# V1_1.net
KiCad netlist of a schematic drawn in Altium Designer
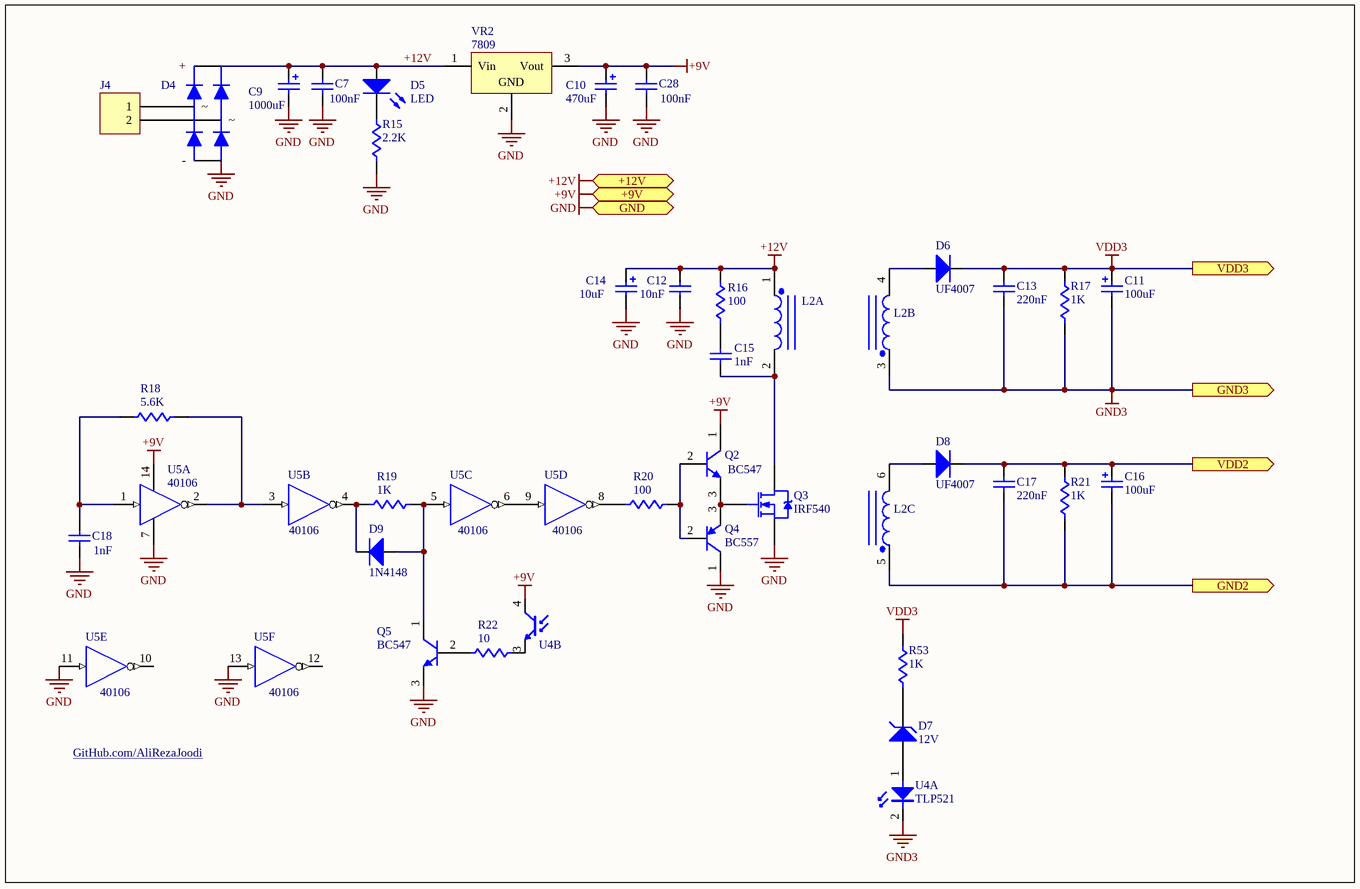
[diagram p0: V1.1.SchDoc]

(export (version "E")
  (design (tool "Eeschema 10.0.6"))
  (components
    (comp (ref "C7")
      (value "100nF")
      (footprint "CAPNTO2.54-3.05x1.78A")
      (description "Capacitor")
      (fields
        (field (name "MANUFACTURER") "Generic Components")
        (field (name "Comment") "Cap")
        (field (name "PUBLISHER") "Altium Limited")
      )
      (libsource (lib "Miscellaneous Devices") (part "Cap"))
    )
    (comp (ref "C9")
      (value "1000uF")
      (footprint "CAPPR5-10x12.5")
      (description "Polarized Capacitor (Radial)")
      (fields
        (field (name "MANUFACTURER") "Generic Components")
        (field (name "Comment") "Cap Pol1")
        (field (name "PUBLISHER") "Altium Limited")
      )
      (libsource (lib "Miscellaneous Devices") (part "Cap Pol1"))
    )
    (comp (ref "C10")
      (value "470uF")
      (footprint "CAPPR5-10x12.5")
      (description "Polarized Capacitor (Radial)")
      (fields
        (field (name "MANUFACTURER") "Generic Components")
        (field (name "Comment") "Cap Pol1")
        (field (name "PUBLISHER") "Altium Limited")
      )
      (libsource (lib "Miscellaneous Devices") (part "Cap Pol1"))
    )
    (comp (ref "C11")
      (value "100uF")
      (footprint "CAPPR2.5-6.3x5")
      (description "Polarized Capacitor (Radial)")
      (fields
        (field (name "MANUFACTURER") "Generic Components")
        (field (name "Comment") "Cap Pol1")
        (field (name "PUBLISHER") "Altium Limited")
      )
      (libsource (lib "Miscellaneous Devices") (part "Cap Pol1"))
    )
    (comp (ref "C12")
      (value "10nF")
      (footprint "CAPNTO2.54-3.05x1.78A")
      (description "Capacitor")
      (fields
        (field (name "MANUFACTURER") "Generic Components")
        (field (name "Comment") "Cap")
        (field (name "PUBLISHER") "Altium Limited")
      )
      (libsource (lib "Miscellaneous Devices") (part "Cap"))
    )
    (comp (ref "C13")
      (value "220nF")
      (footprint "CAPNTO5.08-7.37x3.94")
      (description "Capacitor")
      (fields
        (field (name "MANUFACTURER") "Generic Components")
        (field (name "Comment") "Cap")
        (field (name "PUBLISHER") "Altium Limited")
      )
      (libsource (lib "Miscellaneous Devices") (part "Cap"))
    )
    (comp (ref "C14")
      (value "10uF")
      (footprint "CAPPR2.5-6.3x5")
      (description "Polarized Capacitor (Radial)")
      (fields
        (field (name "MANUFACTURER") "Generic Components")
        (field (name "Comment") "Cap Pol1")
        (field (name "PUBLISHER") "Altium Limited")
      )
      (libsource (lib "Miscellaneous Devices") (part "Cap Pol1"))
    )
    (comp (ref "C15")
      (value "1nF")
      (footprint "CAPNTO2.54-3.56x2.03")
      (description "Capacitor")
      (fields
        (field (name "MANUFACTURER") "Generic Components")
        (field (name "Comment") "Cap")
        (field (name "PUBLISHER") "Altium Limited")
      )
      (libsource (lib "Miscellaneous Devices") (part "Cap"))
    )
    (comp (ref "C16")
      (value "100uF")
      (footprint "CAPPR2.5-6.3x5")
      (description "Polarized Capacitor (Radial)")
      (fields
        (field (name "MANUFACTURER") "Generic Components")
        (field (name "Comment") "Cap Pol1")
        (field (name "PUBLISHER") "Altium Limited")
      )
      (libsource (lib "Miscellaneous Devices") (part "Cap Pol1"))
    )
    (comp (ref "C17")
      (value "220nF")
      (footprint "CAPNTO5.08-7.37x3.94")
      (description "Capacitor")
      (fields
        (field (name "MANUFACTURER") "Generic Components")
        (field (name "Comment") "Cap")
        (field (name "PUBLISHER") "Altium Limited")
      )
      (libsource (lib "Miscellaneous Devices") (part "Cap"))
    )
    (comp (ref "C18")
      (value "1nF")
      (footprint "CAPNTO2.54-3.05x1.78A")
      (description "Capacitor")
      (fields
        (field (name "MANUFACTURER") "Generic Components")
        (field (name "Comment") "Cap")
        (field (name "PUBLISHER") "Altium Limited")
      )
      (libsource (lib "Miscellaneous Devices") (part "Cap"))
    )
    (comp (ref "C28")
      (value "100nF")
      (footprint "CAPNTO2.54-3.05x1.78A")
      (description "Capacitor")
      (fields
        (field (name "MANUFACTURER") "Generic Components")
        (field (name "Comment") "Cap")
        (field (name "PUBLISHER") "Altium Limited")
      )
      (libsource (lib "Miscellaneous Devices") (part "Cap"))
    )
    (comp (ref "D4")
      (value "Bridge_1")
      (footprint "KBP")
      (description "Full Wave Diode Bridge")
      (fields (field (name "MANUFACTURER") "Generic Components") (field (name "PUBLISHER") "Altium Limited"))
      (libsource (lib "my Libraries") (part "Bridge_1"))
    )
    (comp (ref "D5")
      (value "LED")
      (footprint "LED-5mm_Red")
      (description "Typical INFRARED GaAs LED")
      (fields (field (name "MANUFACTURER") "Generic Components") (field (name "PUBLISHER") "Altium Limited"))
      (libsource (lib "Miscellaneous Devices") (part "LED"))
    )
    (comp (ref "D6")
      (value "UF4007")
      (footprint "DIODE-0.4")
      (description "Default Diode")
      (fields (field (name "MANUFACTURER") "Generic Components") (field (name "PUBLISHER") "Altium Limited"))
      (libsource (lib "Miscellaneous Devices") (part "Diode"))
    )
    (comp (ref "D7")
      (value "12V")
      (footprint "DIODE0.4_Glass")
      (description "Zener Diode")
      (fields
        (field (name "MANUFACTURER") "Generic Components")
        (field (name "Comment") "D Zener")
        (field (name "PUBLISHER") "Altium Limited")
      )
      (libsource (lib "Miscellaneous Devices") (part "D Zener"))
    )
    (comp (ref "D8")
      (value "UF4007")
      (footprint "DIODE-0.4")
      (description "Default Diode")
      (fields (field (name "MANUFACTURER") "Generic Components") (field (name "PUBLISHER") "Altium Limited"))
      (libsource (lib "Miscellaneous Devices") (part "Diode"))
    )
    (comp (ref "D9")
      (value "1N4148")
      (footprint "DIODE0.4_Glass")
      (description "Default Diode")
      (fields (field (name "MANUFACTURER") "Generic Components") (field (name "PUBLISHER") "Altium Limited"))
      (libsource (lib "Miscellaneous Devices") (part "Diode"))
    )
    (comp (ref "J4")
      (value "Header 2")
      (footprint "Fonics_2PIN_1")
      (description "Header, 2-Pin")
      (fields (field (name "PUBLISHER") "Altium Limited"))
      (libsource (lib "Miscellaneous Connectors") (part "Header 2"))
    )
    (comp (ref "L2")
      (value "Inductor 3")
      (footprint "INDUCTOR3")
      (fields (field (name "PUBLISHER") "Altium Limited"))
      (libsource (lib "my Libraries") (part "Inductor 3"))
    )
    (comp (ref "Q2")
      (value "NPN")
      (footprint "TO92C")
      (description "Silicon Bipolar Transistor")
      (fields (field (name "DEVICE") "BC547"))
      (libsource (lib "my Libraries") (part "NPN"))
    )
    (comp (ref "Q3")
      (value "IRF540")
      (footprint "TO220V")
      (description "31A, 80V, 0.077 Ohm, N-Channel Power MOSFET")
      (fields (field (name "PUBLISHER") "Altium Limited"))
      (libsource (lib "Intersil Discrete MOSFET") (part "IRFP141"))
    )
    (comp (ref "Q4")
      (value "BC557")
      (footprint "TO92C")
      (description "PNP Bipolar Transistor")
      (fields (field (name "MANUFACTURER") "Generic Components") (field (name "PUBLISHER") "Altium Limited"))
      (libsource (lib "Miscellaneous Devices") (part "PNP"))
    )
    (comp (ref "Q5")
      (value "BC547")
      (footprint "TO92C")
      (description "NPN Bipolar Transistor")
      (fields
        (field (name "MANUFACTURER") "Generic Components")
        (field (name "Comment") "NPN")
        (field (name "PUBLISHER") "Altium Limited")
      )
      (libsource (lib "Miscellaneous Devices") (part "NPN"))
    )
    (comp (ref "R15")
      (value "2.2K")
      (footprint "AXIAL-0.4")
      (description "Resistor")
      (fields
        (field (name "MANUFACTURER") "Generic Components")
        (field (name "Comment") "Res1")
        (field (name "PUBLISHER") "Altium Limited")
      )
      (libsource (lib "Miscellaneous Devices") (part "Res1"))
    )
    (comp (ref "R16")
      (value "100")
      (footprint "AXIAL-0.4")
      (description "Resistor")
      (fields
        (field (name "MANUFACTURER") "Generic Components")
        (field (name "Comment") "Res1")
        (field (name "PUBLISHER") "Altium Limited")
      )
      (libsource (lib "Miscellaneous Devices") (part "Res1"))
    )
    (comp (ref "R17")
      (value "1K")
      (footprint "AXIAL-0.4")
      (description "Resistor")
      (fields
        (field (name "MANUFACTURER") "Generic Components")
        (field (name "Comment") "Res1")
        (field (name "PUBLISHER") "Altium Limited")
      )
      (libsource (lib "Miscellaneous Devices") (part "Res1"))
    )
    (comp (ref "R18")
      (value "5.6K")
      (footprint "AXIAL-0.4")
      (description "Resistor")
      (fields
        (field (name "MANUFACTURER") "Generic Components")
        (field (name "Comment") "Res1")
        (field (name "PUBLISHER") "Altium Limited")
      )
      (libsource (lib "Miscellaneous Devices") (part "Res1"))
    )
    (comp (ref "R19")
      (value "1K")
      (footprint "AXIAL-0.4")
      (description "Resistor")
      (fields
        (field (name "MANUFACTURER") "Generic Components")
        (field (name "Comment") "Res1")
        (field (name "PUBLISHER") "Altium Limited")
      )
      (libsource (lib "Miscellaneous Devices") (part "Res1"))
    )
    (comp (ref "R20")
      (value "100")
      (footprint "AXIAL-0.4")
      (description "Resistor")
      (fields
        (field (name "MANUFACTURER") "Generic Components")
        (field (name "Comment") "Res1")
        (field (name "PUBLISHER") "Altium Limited")
      )
      (libsource (lib "Miscellaneous Devices") (part "Res1"))
    )
    (comp (ref "R21")
      (value "1K")
      (footprint "AXIAL-0.4")
      (description "Resistor")
      (fields
        (field (name "MANUFACTURER") "Generic Components")
        (field (name "Comment") "Res1")
        (field (name "PUBLISHER") "Altium Limited")
      )
      (libsource (lib "Miscellaneous Devices") (part "Res1"))
    )
    (comp (ref "R22")
      (value "10")
      (footprint "AXIAL-0.4")
      (description "Resistor")
      (fields
        (field (name "MANUFACTURER") "Generic Components")
        (field (name "Comment") "Res1")
        (field (name "PUBLISHER") "Altium Limited")
      )
      (libsource (lib "Miscellaneous Devices") (part "Res1"))
    )
    (comp (ref "R53")
      (value "1K")
      (footprint "AXIAL-0.4")
      (description "Resistor")
      (fields
        (field (name "MANUFACTURER") "Generic Components")
        (field (name "Comment") "Res1")
        (field (name "PUBLISHER") "Altium Limited")
      )
      (libsource (lib "Miscellaneous Devices") (part "Res1"))
    )
    (comp (ref "U4")
      (value "TLP521")
      (footprint "DIP-4")
      (fields (field (name "Comment") "Optoisolator") (field (name "PUBLISHER") "Altium Limited"))
      (libsource (lib "my Libraries") (part "Optoisolator"))
    )
    (comp (ref "U5")
      (value "40106")
      (footprint "DIP14")
      (description "Hex inverting Schmitt trigger, 14-Pin")
      (fields (field (name "Comment") "U?") (field (name "PUBLISHER") "Altium Limited"))
      (libsource (lib "my Libraries") (part "40106"))
    )
    (comp (ref "VR2")
      (value "7809")
      (footprint "TO220V")
      (description "Voltage Regulator")
      (fields
        (field (name "MANUFACTURER") "Generic Components")
        (field (name "Comment") "Volt Reg")
        (field (name "PUBLISHER") "Altium Limited")
      )
      (libsource (lib "my Libraries") (part "Volt Reg"))
    )
  )
  (nets
    (net (code "1") (name "+9V") (class "Default")
      (node (ref "C10") (pin "1") (pinfunction "1_1") (pintype "passive"))
      (node (ref "C28") (pin "2") (pinfunction "2_2") (pintype "passive"))
      (node (ref "Q2") (pin "1") (pinfunction "C_1") (pintype "passive"))
      (node (ref "U4") (pin "4") (pinfunction "C_4") (pintype "passive"))
      (node (ref "U5") (pin "14") (pinfunction "VDD_14") (pintype "passive"))
      (node (ref "VR2") (pin "3") (pinfunction "Vout_3") (pintype "passive"))
    )
    (net (code "2") (name "+12V") (class "Default")
      (node (ref "C12") (pin "2") (pinfunction "2_2") (pintype "passive"))
      (node (ref "C14") (pin "1") (pinfunction "1_1") (pintype "passive"))
      (node (ref "C7") (pin "2") (pinfunction "2_2") (pintype "passive"))
      (node (ref "C9") (pin "1") (pinfunction "1_1") (pintype "passive"))
      (node (ref "D4") (pin "3") (pinfunction "+_3") (pintype "passive"))
      (node (ref "D5") (pin "1") (pinfunction "A_1") (pintype "passive"))
      (node (ref "L2") (pin "1") (pinfunction "1_1") (pintype "passive"))
      (node (ref "R16") (pin "1") (pinfunction "1_1") (pintype "passive"))
      (node (ref "VR2") (pin "1") (pinfunction "Vin_1") (pintype "passive"))
    )
    (net (code "3") (name "/GND2") (class "Default")
      (node (ref "C16") (pin "2") (pinfunction "2_2") (pintype "passive"))
      (node (ref "C17") (pin "1") (pinfunction "1_1") (pintype "passive"))
      (node (ref "L2") (pin "5") (pinfunction "5_5") (pintype "passive"))
      (node (ref "R21") (pin "2") (pinfunction "2_2") (pintype "passive"))
    )
    (net (code "4") (name "/VDD2") (class "Default")
      (node (ref "C16") (pin "1") (pinfunction "1_1") (pintype "passive"))
      (node (ref "C17") (pin "2") (pinfunction "2_2") (pintype "passive"))
      (node (ref "D8") (pin "2") (pinfunction "K_2") (pintype "passive"))
      (node (ref "R21") (pin "1") (pinfunction "1_1") (pintype "passive"))
    )
    (net (code "5") (name "GND") (class "Default")
      (node (ref "C10") (pin "2") (pinfunction "2_2") (pintype "passive"))
      (node (ref "C12") (pin "1") (pinfunction "1_1") (pintype "passive"))
      (node (ref "C14") (pin "2") (pinfunction "2_2") (pintype "passive"))
      (node (ref "C18") (pin "1") (pinfunction "1_1") (pintype "passive"))
      (node (ref "C28") (pin "1") (pinfunction "1_1") (pintype "passive"))
      (node (ref "C7") (pin "1") (pinfunction "1_1") (pintype "passive"))
      (node (ref "C9") (pin "2") (pinfunction "2_2") (pintype "passive"))
      (node (ref "D4") (pin "1") (pinfunction "-_1") (pintype "passive"))
      (node (ref "Q3") (pin "3") (pinfunction "S_3") (pintype "passive"))
      (node (ref "Q4") (pin "1") (pinfunction "C_1") (pintype "passive"))
      (node (ref "Q5") (pin "3") (pinfunction "E_3") (pintype "passive"))
      (node (ref "R15") (pin "2") (pinfunction "2_2") (pintype "passive"))
      (node (ref "U5") (pin "11") (pinfunction "I_11") (pintype "input"))
      (node (ref "U5") (pin "13") (pinfunction "I_13") (pintype "input"))
      (node (ref "U5") (pin "7") (pinfunction "VSS_7") (pintype "power_in"))
      (node (ref "VR2") (pin "2") (pinfunction "GND_2") (pintype "passive"))
    )
    (net (code "6") (name "GND3") (class "Default")
      (node (ref "C11") (pin "2") (pinfunction "2_2") (pintype "passive"))
      (node (ref "C13") (pin "1") (pinfunction "1_1") (pintype "passive"))
      (node (ref "L2") (pin "3") (pinfunction "3_3") (pintype "passive"))
      (node (ref "R17") (pin "2") (pinfunction "2_2") (pintype "passive"))
      (node (ref "U4") (pin "2") (pinfunction "K_2") (pintype "power_in"))
    )
    (net (code "7") (name "Net-(C15-Pad2)") (class "Default")
      (node (ref "C15") (pin "2") (pinfunction "2_2") (pintype "passive"))
      (node (ref "R16") (pin "2") (pinfunction "2_2") (pintype "passive"))
    )
    (net (code "8") (name "Net-(D4-~-Pad2)") (class "Default")
      (node (ref "D4") (pin "2") (pinfunction "~_2") (pintype "passive"))
      (node (ref "J4") (pin "2") (pinfunction "2_2") (pintype "passive"))
    )
    (net (code "9") (name "Net-(D4-~-Pad4)") (class "Default")
      (node (ref "D4") (pin "4") (pinfunction "~_4") (pintype "passive"))
      (node (ref "J4") (pin "1") (pinfunction "1_1") (pintype "passive"))
    )
    (net (code "10") (name "Net-(D5-K)") (class "Default")
      (node (ref "D5") (pin "2") (pinfunction "K_2") (pintype "passive"))
      (node (ref "R15") (pin "1") (pinfunction "1_1") (pintype "passive"))
    )
    (net (code "11") (name "Net-(D6-A)") (class "Default")
      (node (ref "D6") (pin "1") (pinfunction "A_1") (pintype "passive"))
      (node (ref "L2") (pin "4") (pinfunction "4_4") (pintype "passive"))
    )
    (net (code "12") (name "Net-(D7-A)") (class "Default")
      (node (ref "D7") (pin "1") (pinfunction "A_1") (pintype "passive"))
      (node (ref "U4") (pin "1") (pinfunction "A_1") (pintype "power_in"))
    )
    (net (code "13") (name "Net-(D7-K)") (class "Default")
      (node (ref "D7") (pin "2") (pinfunction "K_2") (pintype "passive"))
      (node (ref "R53") (pin "2") (pinfunction "2_2") (pintype "passive"))
    )
    (net (code "14") (name "Net-(D8-A)") (class "Default")
      (node (ref "D8") (pin "1") (pinfunction "A_1") (pintype "passive"))
      (node (ref "L2") (pin "6") (pinfunction "6_6") (pintype "passive"))
    )
    (net (code "15") (name "Net-(D9-A)") (class "Default")
      (node (ref "D9") (pin "1") (pinfunction "A_1") (pintype "passive"))
      (node (ref "Q5") (pin "1") (pinfunction "C_1") (pintype "passive"))
      (node (ref "R19") (pin "1") (pinfunction "1_1") (pintype "passive"))
      (node (ref "U5") (pin "5") (pinfunction "I_5") (pintype "input"))
    )
    (net (code "16") (name "Net-(D9-K)") (class "Default")
      (node (ref "D9") (pin "2") (pinfunction "K_2") (pintype "passive"))
      (node (ref "R19") (pin "2") (pinfunction "2_2") (pintype "passive"))
      (node (ref "U5") (pin "4") (pinfunction "~{O}_4") (pintype "output"))
    )
    (net (code "17") (name "Net-(Q2-B)") (class "Default")
      (node (ref "Q2") (pin "2") (pinfunction "B_2") (pintype "passive"))
      (node (ref "Q4") (pin "2") (pinfunction "B_2") (pintype "passive"))
      (node (ref "R20") (pin "2") (pinfunction "2_2") (pintype "passive"))
    )
    (net (code "18") (name "Net-(Q2-E)") (class "Default")
      (node (ref "Q2") (pin "3") (pinfunction "E_3") (pintype "passive"))
      (node (ref "Q3") (pin "1") (pinfunction "G_1") (pintype "passive"))
      (node (ref "Q4") (pin "3") (pinfunction "E_3") (pintype "passive"))
    )
    (net (code "19") (name "Net-(Q3-D)") (class "Default")
      (node (ref "C15") (pin "1") (pinfunction "1_1") (pintype "passive"))
      (node (ref "L2") (pin "2") (pinfunction "2_2") (pintype "passive"))
      (node (ref "Q3") (pin "2") (pinfunction "D_2") (pintype "passive"))
    )
    (net (code "20") (name "Net-(Q5-B)") (class "Default")
      (node (ref "Q5") (pin "2") (pinfunction "B_2") (pintype "passive"))
      (node (ref "R22") (pin "1") (pinfunction "1_1") (pintype "passive"))
    )
    (net (code "21") (name "Net-(U4B-E)") (class "Default")
      (node (ref "R22") (pin "2") (pinfunction "2_2") (pintype "passive"))
      (node (ref "U4") (pin "3") (pinfunction "E_3") (pintype "passive"))
    )
    (net (code "22") (name "Net-(U5A-I)") (class "Default")
      (node (ref "C18") (pin "2") (pinfunction "2_2") (pintype "passive"))
      (node (ref "R18") (pin "2") (pinfunction "2_2") (pintype "passive"))
      (node (ref "U5") (pin "1") (pinfunction "I_1") (pintype "input"))
    )
    (net (code "23") (name "Net-(U5A-~{O})") (class "Default")
      (node (ref "R18") (pin "1") (pinfunction "1_1") (pintype "passive"))
      (node (ref "U5") (pin "2") (pinfunction "~{O}_2") (pintype "output"))
      (node (ref "U5") (pin "3") (pinfunction "I_3") (pintype "input"))
    )
    (net (code "24") (name "Net-(U5C-~{O})") (class "Default")
      (node (ref "U5") (pin "6") (pinfunction "~{O}_6") (pintype "output"))
      (node (ref "U5") (pin "9") (pinfunction "I_9") (pintype "input"))
    )
    (net (code "25") (name "Net-(U5D-~{O})") (class "Default")
      (node (ref "R20") (pin "1") (pinfunction "1_1") (pintype "passive"))
      (node (ref "U5") (pin "8") (pinfunction "~{O}_8") (pintype "output"))
    )
    (net (code "26") (name "VDD3") (class "Default")
      (node (ref "C11") (pin "1") (pinfunction "1_1") (pintype "passive"))
      (node (ref "C13") (pin "2") (pinfunction "2_2") (pintype "passive"))
      (node (ref "D6") (pin "2") (pinfunction "K_2") (pintype "passive"))
      (node (ref "R17") (pin "1") (pinfunction "1_1") (pintype "passive"))
      (node (ref "R53") (pin "1") (pinfunction "1_1") (pintype "passive"))
    )
    (net (code "27") (name "unconnected-(U5E-~{O}-Pad10)") (class "Default")
      (node (ref "U5") (pin "10") (pinfunction "~{O}_10") (pintype "output"))
    )
    (net (code "28") (name "unconnected-(U5F-~{O}-Pad12)") (class "Default")
      (node (ref "U5") (pin "12") (pinfunction "~{O}_12") (pintype "output"))
    )
  )
)
